# Sheet1.net
KiCad netlist of a schematic drawn in Altium Designer
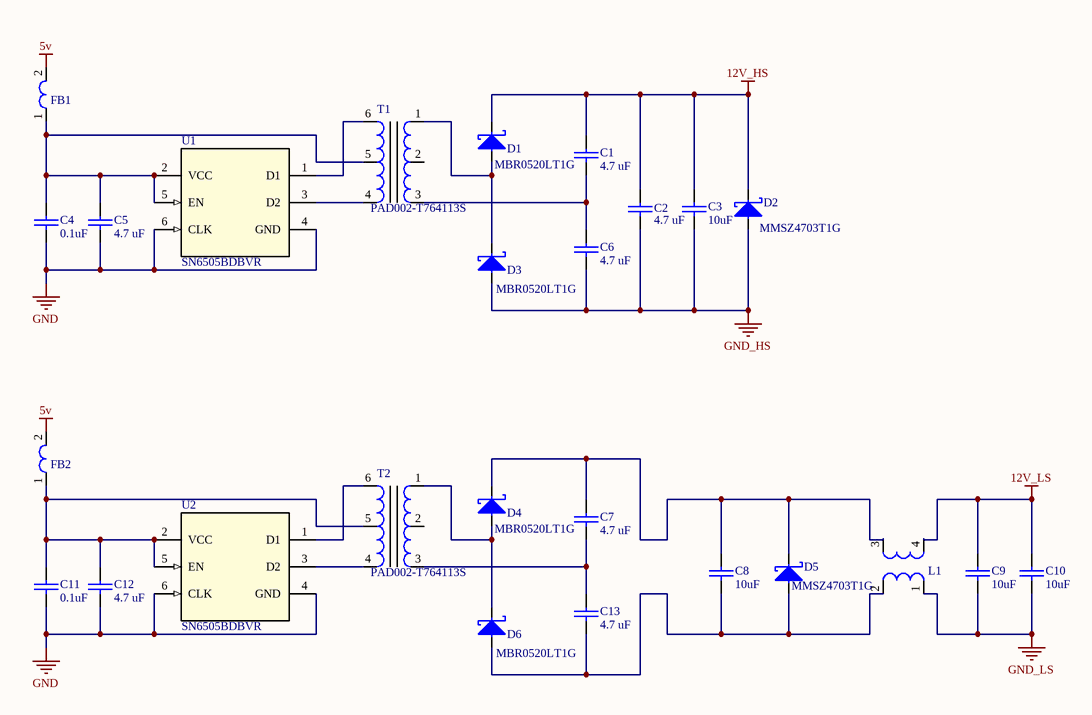
[diagram p0: Sheet1.SchDoc]

(export (version "E")
  (design (tool "Eeschema 10.0.6"))
  (components
    (comp (ref "C1")
      (value "4.7 uF")
      (footprint "0603_cap")
      (description "CAP CER 4.7UF 25V X5R 0603")
      (fields
        (field (name "MANUFACTURER") "Murata Electronics")
        (field (name "MANUFACTURER PART NUMBER") "GRM188R61E475KE11D")
      )
      (libsource (lib "shared_lib") (part "CAP_4.7UF_25V_0603"))
    )
    (comp (ref "C2")
      (value "4.7 uF")
      (footprint "0603_cap")
      (description "CAP CER 4.7UF 25V X5R 0603")
      (fields
        (field (name "MANUFACTURER") "Murata Electronics")
        (field (name "MANUFACTURER PART NUMBER") "GRM188R61E475KE11D")
      )
      (libsource (lib "shared_lib") (part "CAP_4.7UF_25V_0603"))
    )
    (comp (ref "C3")
      (value "10uF")
      (footprint "0805_cap")
      (description "25V 10uF X5R ±10% 0805 Multilayer Ceramic Capacitors MLCC - SMD/SMT ROHS")
      (fields
        (field (name "MANUFACTURER") "Samsung Electro-Mechanics")
        (field (name "MANUFACTURER PART NUMBER") "CL21A106KAYNNNE")
      )
      (libsource (lib "shared_lib") (part "Cap_10uF_0805_25V_"))
    )
    (comp (ref "C4")
      (value "0.1uF")
      (footprint "0603_cap")
      (description "50V 100nF Y5V -20%~+80% 0603 Multilayer Ceramic Capacitors MLCC - SMD/SMT ROHS")
      (fields
        (field (name "MANUFACTURER") "Walsin Tech Corp")
        (field (name "MANUFACTURER PART NUMBER") "0603F104Z500CT")
      )
      (libsource (lib "shared_lib") (part "Cap_0.1uF_0603_50V"))
    )
    (comp (ref "C5")
      (value "4.7 uF")
      (footprint "0603_cap")
      (description "CAP CER 4.7UF 25V X5R 0603")
      (fields
        (field (name "MANUFACTURER") "Murata Electronics")
        (field (name "MANUFACTURER PART NUMBER") "GRM188R61E475KE11D")
      )
      (libsource (lib "shared_lib") (part "CAP_4.7UF_25V_0603"))
    )
    (comp (ref "C6")
      (value "4.7 uF")
      (footprint "0603_cap")
      (description "CAP CER 4.7UF 25V X5R 0603")
      (fields
        (field (name "MANUFACTURER") "Murata Electronics")
        (field (name "MANUFACTURER PART NUMBER") "GRM188R61E475KE11D")
      )
      (libsource (lib "shared_lib") (part "CAP_4.7UF_25V_0603"))
    )
    (comp (ref "C7")
      (value "4.7 uF")
      (footprint "0603_cap")
      (description "CAP CER 4.7UF 25V X5R 0603")
      (fields
        (field (name "MANUFACTURER") "Murata Electronics")
        (field (name "MANUFACTURER PART NUMBER") "GRM188R61E475KE11D")
      )
      (libsource (lib "shared_lib") (part "CAP_4.7UF_25V_0603"))
    )
    (comp (ref "C8")
      (value "10uF")
      (footprint "0805_cap")
      (description "25V 10uF X5R ±10% 0805 Multilayer Ceramic Capacitors MLCC - SMD/SMT ROHS")
      (fields
        (field (name "MANUFACTURER") "Samsung Electro-Mechanics")
        (field (name "MANUFACTURER PART NUMBER") "CL21A106KAYNNNE")
      )
      (libsource (lib "shared_lib") (part "Cap_10uF_0805_25V_"))
    )
    (comp (ref "C9")
      (value "10uF")
      (footprint "0805_cap")
      (description "25V 10uF X5R ±10% 0805 Multilayer Ceramic Capacitors MLCC - SMD/SMT ROHS")
      (fields
        (field (name "MANUFACTURER") "Samsung Electro-Mechanics")
        (field (name "MANUFACTURER PART NUMBER") "CL21A106KAYNNNE")
      )
      (libsource (lib "shared_lib") (part "Cap_10uF_0805_25V_"))
    )
    (comp (ref "C10")
      (value "10uF")
      (footprint "0805_cap")
      (description "25V 10uF X5R ±10% 0805 Multilayer Ceramic Capacitors MLCC - SMD/SMT ROHS")
      (fields
        (field (name "MANUFACTURER") "Samsung Electro-Mechanics")
        (field (name "MANUFACTURER PART NUMBER") "CL21A106KAYNNNE")
      )
      (libsource (lib "shared_lib") (part "Cap_10uF_0805_25V_"))
    )
    (comp (ref "C11")
      (value "0.1uF")
      (footprint "0603_cap")
      (description "50V 100nF Y5V -20%~+80% 0603 Multilayer Ceramic Capacitors MLCC - SMD/SMT ROHS")
      (fields
        (field (name "MANUFACTURER") "Walsin Tech Corp")
        (field (name "MANUFACTURER PART NUMBER") "0603F104Z500CT")
      )
      (libsource (lib "shared_lib") (part "Cap_0.1uF_0603_50V"))
    )
    (comp (ref "C12")
      (value "4.7 uF")
      (footprint "0603_cap")
      (description "CAP CER 4.7UF 25V X5R 0603")
      (fields
        (field (name "MANUFACTURER") "Murata Electronics")
        (field (name "MANUFACTURER PART NUMBER") "GRM188R61E475KE11D")
      )
      (libsource (lib "shared_lib") (part "CAP_4.7UF_25V_0603"))
    )
    (comp (ref "C13")
      (value "4.7 uF")
      (footprint "0603_cap")
      (description "CAP CER 4.7UF 25V X5R 0603")
      (fields
        (field (name "MANUFACTURER") "Murata Electronics")
        (field (name "MANUFACTURER PART NUMBER") "GRM188R61E475KE11D")
      )
      (libsource (lib "shared_lib") (part "CAP_4.7UF_25V_0603"))
    )
    (comp (ref "D1")
      (value "DIODE_SCHOTTKY_20V")
      (footprint "SOD-123_ONS")
      (description "DIODE SCHOTTKY 20V 500MA SOD123")
      (fields (field (name "MANUFACTURER") "onsemi") (field (name "MANUFACTURER PART NUMBER") "MBR0520LT1G"))
      (libsource (lib "shared_lib") (part "DIODE_SCHOTTKY_20V"))
    )
    (comp (ref "D2")
      (value "DIODE_ZENER_16V")
      (footprint "SOD-123_ONS")
      (description "DIODE ZENER 16V 500MW SOD123")
      (fields (field (name "MANUFACTURER") "onsemi") (field (name "MANUFACTURER PART NUMBER") "MMSZ4703T1G"))
      (libsource (lib "shared_lib") (part "DIODE_ZENER_16V"))
    )
    (comp (ref "D3")
      (value "DIODE_SCHOTTKY_20V")
      (footprint "SOD-123_ONS")
      (description "DIODE SCHOTTKY 20V 500MA SOD123")
      (fields (field (name "MANUFACTURER") "onsemi") (field (name "MANUFACTURER PART NUMBER") "MBR0520LT1G"))
      (libsource (lib "shared_lib") (part "DIODE_SCHOTTKY_20V"))
    )
    (comp (ref "D4")
      (value "DIODE_SCHOTTKY_20V")
      (footprint "SOD-123_ONS")
      (description "DIODE SCHOTTKY 20V 500MA SOD123")
      (fields (field (name "MANUFACTURER") "onsemi") (field (name "MANUFACTURER PART NUMBER") "MBR0520LT1G"))
      (libsource (lib "shared_lib") (part "DIODE_SCHOTTKY_20V"))
    )
    (comp (ref "D5")
      (value "DIODE_ZENER_16V")
      (footprint "SOD-123_ONS")
      (description "DIODE ZENER 16V 500MW SOD123")
      (fields (field (name "MANUFACTURER") "onsemi") (field (name "MANUFACTURER PART NUMBER") "MMSZ4703T1G"))
      (libsource (lib "shared_lib") (part "DIODE_ZENER_16V"))
    )
    (comp (ref "D6")
      (value "DIODE_SCHOTTKY_20V")
      (footprint "SOD-123_ONS")
      (description "DIODE SCHOTTKY 20V 500MA SOD123")
      (fields (field (name "MANUFACTURER") "onsemi") (field (name "MANUFACTURER PART NUMBER") "MBR0520LT1G"))
      (libsource (lib "shared_lib") (part "DIODE_SCHOTTKY_20V"))
    )
    (comp (ref "FB1")
      (value "FERRITE_BEAD_600_OHM")
      (footprint "MH1608")
      (description "FERRITE BEAD 600 OHM 0603 4LN")
      (fields
        (field (name "MANUFACTURER") "Bourns Inc.")
        (field (name "MANUFACTURER PART NUMBER") "MH1608-601Y")
      )
      (libsource (lib "shared_lib") (part "FERRITE_BEAD_600_OHM"))
    )
    (comp (ref "FB2")
      (value "FERRITE_BEAD_600_OHM")
      (footprint "MH1608")
      (description "FERRITE BEAD 600 OHM 0603 4LN")
      (fields
        (field (name "MANUFACTURER") "Bourns Inc.")
        (field (name "MANUFACTURER PART NUMBER") "MH1608-601Y")
      )
      (libsource (lib "shared_lib") (part "FERRITE_BEAD_600_OHM"))
    )
    (comp (ref "L1")
      (value "CMC_300MA_2LN_360_OHM_SMD")
      (footprint "SRF2012-361YA")
      (description "2 Obturador de modo común de línea Montaje en superficie 360 Ohms @ 100 MHz 300mA DCR 500mOhm")
      (fields
        (field (name "MANUFACTURER") "Bourns Inc.")
        (field (name "MANUFACTURER PART NUMBER") "SRF2012-361YA")
      )
      (libsource (lib "shared_lib") (part "CMC_300MA_2LN_360_OHM_SMD"))
    )
    (comp (ref "T1")
      (value "PAD002-T764113S")
      (footprint "PAD002-T764113S")
      (description "XFMR FWD P-P DC/DC CONV 475UH SM")
      (fields (field (name "MANUFACTURER") "Bourns Inc."))
      (libsource (lib "shared_lib") (part "TRANSFORMER_SMPS_XFMR_FWD"))
    )
    (comp (ref "T2")
      (value "PAD002-T764113S")
      (footprint "PAD002-T764113S")
      (description "XFMR FWD P-P DC/DC CONV 475UH SM")
      (fields (field (name "MANUFACTURER") "Bourns Inc."))
      (libsource (lib "shared_lib") (part "TRANSFORMER_SMPS_XFMR_FWD"))
    )
    (comp (ref "U1")
      (value "SN6505BDBVR")
      (footprint "IC TRANSFORMER DRIVER 6SOT-23")
      (description "IC TRANSFORMER DRIVER 6SOT-23")
      (fields (field (name "MANUFACTURER") "Texas Instruments"))
      (libsource (lib "shared_lib") (part "IC_TRANSFORMER_DRIVER_6SOT-23"))
    )
    (comp (ref "U2")
      (value "SN6505BDBVR")
      (footprint "IC TRANSFORMER DRIVER 6SOT-23")
      (description "IC TRANSFORMER DRIVER 6SOT-23")
      (fields (field (name "MANUFACTURER") "Texas Instruments"))
      (libsource (lib "shared_lib") (part "IC_TRANSFORMER_DRIVER_6SOT-23"))
    )
  )
  (nets
    (net (code "1") (name "5v") (class "Default")
      (node (ref "FB1") (pin "2") (pinfunction "2_2") (pintype "passive"))
      (node (ref "FB2") (pin "2") (pinfunction "2_2") (pintype "passive"))
    )
    (net (code "2") (name "12V_HS") (class "Default")
      (node (ref "C1") (pin "1") (pinfunction "1_1") (pintype "passive"))
      (node (ref "C2") (pin "1") (pinfunction "1_1") (pintype "passive"))
      (node (ref "C3") (pin "1") (pinfunction "1_1") (pintype "passive"))
      (node (ref "D1") (pin "1") (pinfunction "1_1") (pintype "passive"))
      (node (ref "D2") (pin "1") (pinfunction "1_1") (pintype "passive"))
    )
    (net (code "3") (name "12V_LS") (class "Default")
      (node (ref "C10") (pin "1") (pinfunction "1_1") (pintype "passive"))
      (node (ref "C9") (pin "1") (pinfunction "1_1") (pintype "passive"))
      (node (ref "L1") (pin "4") (pinfunction "4_4") (pintype "passive"))
    )
    (net (code "4") (name "GND") (class "Default")
      (node (ref "C11") (pin "2") (pinfunction "2_2") (pintype "passive"))
      (node (ref "C12") (pin "2") (pinfunction "2_2") (pintype "passive"))
      (node (ref "C4") (pin "2") (pinfunction "2_2") (pintype "passive"))
      (node (ref "C5") (pin "2") (pinfunction "2_2") (pintype "passive"))
      (node (ref "U1") (pin "4") (pinfunction "GND_4") (pintype "power_in"))
      (node (ref "U1") (pin "6") (pinfunction "CLK_6") (pintype "input"))
      (node (ref "U2") (pin "4") (pinfunction "GND_4") (pintype "power_in"))
      (node (ref "U2") (pin "6") (pinfunction "CLK_6") (pintype "input"))
    )
    (net (code "5") (name "GND_HS") (class "Default")
      (node (ref "C2") (pin "2") (pinfunction "2_2") (pintype "passive"))
      (node (ref "C3") (pin "2") (pinfunction "2_2") (pintype "passive"))
      (node (ref "C6") (pin "2") (pinfunction "2_2") (pintype "passive"))
      (node (ref "D2") (pin "2") (pinfunction "2_2") (pintype "passive"))
      (node (ref "D3") (pin "2") (pinfunction "2_2") (pintype "passive"))
    )
    (net (code "6") (name "GND_LS") (class "Default")
      (node (ref "C10") (pin "2") (pinfunction "2_2") (pintype "passive"))
      (node (ref "C9") (pin "2") (pinfunction "2_2") (pintype "passive"))
      (node (ref "L1") (pin "1") (pinfunction "1_1") (pintype "passive"))
    )
    (net (code "7") (name "Net-(C1-Pad2)") (class "Default")
      (node (ref "C1") (pin "2") (pinfunction "2_2") (pintype "passive"))
      (node (ref "C6") (pin "1") (pinfunction "1_1") (pintype "passive"))
      (node (ref "T1") (pin "3") (pinfunction "3_3") (pintype "passive"))
    )
    (net (code "8") (name "Net-(C7-Pad1)") (class "Default")
      (node (ref "C7") (pin "1") (pinfunction "1_1") (pintype "passive"))
      (node (ref "C8") (pin "1") (pinfunction "1_1") (pintype "passive"))
      (node (ref "D4") (pin "1") (pinfunction "1_1") (pintype "passive"))
      (node (ref "D5") (pin "1") (pinfunction "1_1") (pintype "passive"))
      (node (ref "L1") (pin "3") (pinfunction "3_3") (pintype "passive"))
    )
    (net (code "9") (name "Net-(C13-Pad1)") (class "Default")
      (node (ref "C13") (pin "1") (pinfunction "1_1") (pintype "passive"))
      (node (ref "C7") (pin "2") (pinfunction "2_2") (pintype "passive"))
      (node (ref "T2") (pin "3") (pinfunction "3_3") (pintype "passive"))
    )
    (net (code "10") (name "Net-(C13-Pad2)") (class "Default")
      (node (ref "C13") (pin "2") (pinfunction "2_2") (pintype "passive"))
      (node (ref "C8") (pin "2") (pinfunction "2_2") (pintype "passive"))
      (node (ref "D5") (pin "2") (pinfunction "2_2") (pintype "passive"))
      (node (ref "D6") (pin "2") (pinfunction "2_2") (pintype "passive"))
      (node (ref "L1") (pin "2") (pinfunction "2_2") (pintype "passive"))
    )
    (net (code "11") (name "Net-(D1-Pad2)") (class "Default")
      (node (ref "D1") (pin "2") (pinfunction "2_2") (pintype "passive"))
      (node (ref "D3") (pin "1") (pinfunction "1_1") (pintype "passive"))
      (node (ref "T1") (pin "1") (pinfunction "1_1") (pintype "passive"))
    )
    (net (code "12") (name "Net-(D4-Pad2)") (class "Default")
      (node (ref "D4") (pin "2") (pinfunction "2_2") (pintype "passive"))
      (node (ref "D6") (pin "1") (pinfunction "1_1") (pintype "passive"))
      (node (ref "T2") (pin "1") (pinfunction "1_1") (pintype "passive"))
    )
    (net (code "13") (name "Net-(U1-D1)") (class "Default")
      (node (ref "T1") (pin "6") (pinfunction "6_6") (pintype "passive"))
      (node (ref "U1") (pin "1") (pinfunction "D1_1") (pintype "open_collector"))
    )
    (net (code "14") (name "Net-(U1-D2)") (class "Default")
      (node (ref "T1") (pin "4") (pinfunction "4_4") (pintype "passive"))
      (node (ref "U1") (pin "3") (pinfunction "D2_3") (pintype "open_collector"))
    )
    (net (code "15") (name "Net-(U1-EN)") (class "Default")
      (node (ref "C4") (pin "1") (pinfunction "1_1") (pintype "passive"))
      (node (ref "C5") (pin "1") (pinfunction "1_1") (pintype "passive"))
      (node (ref "FB1") (pin "1") (pinfunction "1_1") (pintype "passive"))
      (node (ref "T1") (pin "5") (pinfunction "5_5") (pintype "passive"))
      (node (ref "U1") (pin "2") (pinfunction "VCC_2") (pintype "power_in"))
      (node (ref "U1") (pin "5") (pinfunction "EN_5") (pintype "input"))
    )
    (net (code "16") (name "Net-(U2-D1)") (class "Default")
      (node (ref "T2") (pin "6") (pinfunction "6_6") (pintype "passive"))
      (node (ref "U2") (pin "1") (pinfunction "D1_1") (pintype "open_collector"))
    )
    (net (code "17") (name "Net-(U2-D2)") (class "Default")
      (node (ref "T2") (pin "4") (pinfunction "4_4") (pintype "passive"))
      (node (ref "U2") (pin "3") (pinfunction "D2_3") (pintype "open_collector"))
    )
    (net (code "18") (name "Net-(U2-EN)") (class "Default")
      (node (ref "C11") (pin "1") (pinfunction "1_1") (pintype "passive"))
      (node (ref "C12") (pin "1") (pinfunction "1_1") (pintype "passive"))
      (node (ref "FB2") (pin "1") (pinfunction "1_1") (pintype "passive"))
      (node (ref "T2") (pin "5") (pinfunction "5_5") (pintype "passive"))
      (node (ref "U2") (pin "2") (pinfunction "VCC_2") (pintype "power_in"))
      (node (ref "U2") (pin "5") (pinfunction "EN_5") (pintype "input"))
    )
    (net (code "19") (name "unconnected-(T1-Pad2)") (class "Default")
      (node (ref "T1") (pin "2") (pinfunction "2_2") (pintype "passive"))
    )
    (net (code "20") (name "unconnected-(T2-Pad2)") (class "Default")
      (node (ref "T2") (pin "2") (pinfunction "2_2") (pintype "passive"))
    )
  )
)
